# Shift_register.net
KiCad netlist of a schematic drawn in Altium Designer
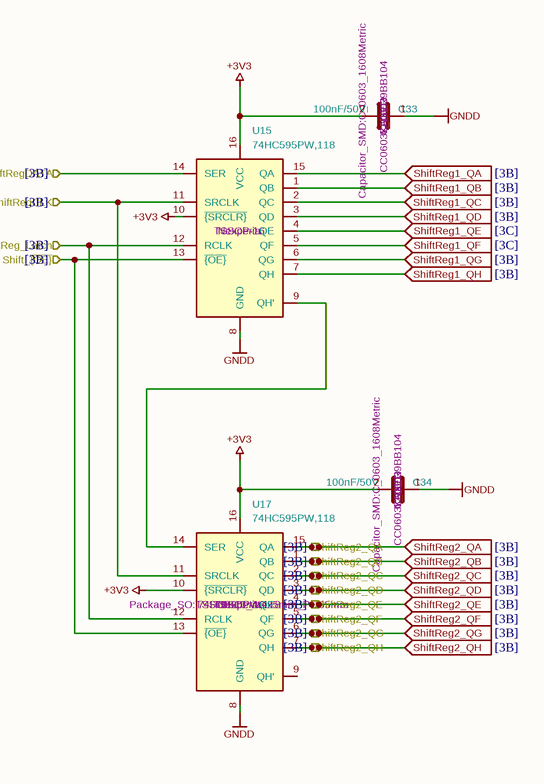
[diagram p0: Shift register.SchDoc]

(export (version "E")
  (design (tool "Eeschema 10.0.6"))
  (components
    (comp (ref "C33")
      (value "100nF/50V")
      (footprint "Capacitor_SMD:C_0603_1608Metric")
      (fields
        (field (name "MP") "CC0603KRX7R9BB104")
        (field (name "MF") "YAGEO")
        (field (name "PACKAGE") "C_0603")
      )
      (libsource (lib "Device") (part "C"))
    )
    (comp (ref "C34")
      (value "100nF/50V")
      (footprint "Capacitor_SMD:C_0603_1608Metric")
      (fields
        (field (name "MP") "CC0603KRX7R9BB104")
        (field (name "MF") "YAGEO")
        (field (name "PACKAGE") "C_0603")
      )
      (libsource (lib "Device") (part "C"))
    )
    (comp (ref "U15")
      (value "74HC595PW,118")
      (footprint "TSSOP-16_4.4x5mm_P0.65mm")
      (fields (field (name "MF") "Nexperia") (field (name "PACKAGE") "TSSOP-16"))
      (libsource (lib "74xx") (part "74HC595"))
    )
    (comp (ref "U17")
      (value "74HC595PW,118")
      (footprint "Package_SO:TSSOP-16_4.4x5mm_P0.65mm")
      (fields
        (field (name "MP") "74HC595PW,118")
        (field (name "MF") "Nexperia")
        (field (name "PACKAGE") "TSSOP-16")
      )
      (libsource (lib "74xx") (part "74HC595"))
    )
  )
  (nets
    (net (code "1") (name "+3V3") (class "Default")
      (node (ref "C33") (pin "2") (pinfunction "2_2") (pintype "passive"))
      (node (ref "C34") (pin "2") (pinfunction "2_2") (pintype "passive"))
      (node (ref "U15") (pin "10") (pinfunction "~{{SRCLR}}_10") (pintype "passive"))
      (node (ref "U15") (pin "16") (pinfunction "VCC_16") (pintype "passive"))
      (node (ref "U17") (pin "10") (pinfunction "~{{SRCLR}}_10") (pintype "passive"))
      (node (ref "U17") (pin "16") (pinfunction "VCC_16") (pintype "passive"))
    )
    (net (code "2") (name "/ShiftReg1_QA") (class "Default")
      (node (ref "U15") (pin "15") (pinfunction "QA_15") (pintype "passive"))
    )
    (net (code "3") (name "/ShiftReg1_QB") (class "Default")
      (node (ref "U15") (pin "1") (pinfunction "QB_1") (pintype "passive"))
    )
    (net (code "4") (name "/ShiftReg1_QC") (class "Default")
      (node (ref "U15") (pin "2") (pinfunction "QC_2") (pintype "passive"))
    )
    (net (code "5") (name "/ShiftReg1_QD") (class "Default")
      (node (ref "U15") (pin "3") (pinfunction "QD_3") (pintype "passive"))
    )
    (net (code "6") (name "/ShiftReg1_QE") (class "Default")
      (node (ref "U15") (pin "4") (pinfunction "QE_4") (pintype "passive"))
    )
    (net (code "7") (name "/ShiftReg1_QF") (class "Default")
      (node (ref "U15") (pin "5") (pinfunction "QF_5") (pintype "passive"))
    )
    (net (code "8") (name "/ShiftReg1_QG") (class "Default")
      (node (ref "U15") (pin "6") (pinfunction "QG_6") (pintype "passive"))
    )
    (net (code "9") (name "/ShiftReg1_QH") (class "Default")
      (node (ref "U15") (pin "7") (pinfunction "QH_7") (pintype "passive"))
    )
    (net (code "10") (name "/ShiftReg2_QA") (class "Default")
      (node (ref "U17") (pin "15") (pinfunction "QA_15") (pintype "passive"))
    )
    (net (code "11") (name "/ShiftReg2_QB") (class "Default")
      (node (ref "U17") (pin "1") (pinfunction "QB_1") (pintype "passive"))
    )
    (net (code "12") (name "/ShiftReg2_QC") (class "Default")
      (node (ref "U17") (pin "2") (pinfunction "QC_2") (pintype "passive"))
    )
    (net (code "13") (name "/ShiftReg2_QD") (class "Default")
      (node (ref "U17") (pin "3") (pinfunction "QD_3") (pintype "passive"))
    )
    (net (code "14") (name "/ShiftReg2_QE") (class "Default")
      (node (ref "U17") (pin "4") (pinfunction "QE_4") (pintype "passive"))
    )
    (net (code "15") (name "/ShiftReg2_QF") (class "Default")
      (node (ref "U17") (pin "5") (pinfunction "QF_5") (pintype "passive"))
    )
    (net (code "16") (name "/ShiftReg2_QG") (class "Default")
      (node (ref "U17") (pin "6") (pinfunction "QG_6") (pintype "passive"))
    )
    (net (code "17") (name "/ShiftReg2_QH") (class "Default")
      (node (ref "U17") (pin "7") (pinfunction "QH_7") (pintype "passive"))
    )
    (net (code "18") (name "/ShiftRegCLK") (class "Default")
      (node (ref "U15") (pin "11") (pinfunction "SRCLK_11") (pintype "passive"))
      (node (ref "U17") (pin "11") (pinfunction "SRCLK_11") (pintype "passive"))
    )
    (net (code "19") (name "/ShiftRegDATA") (class "Default")
      (node (ref "U15") (pin "14") (pinfunction "SER_14") (pintype "passive"))
    )
    (net (code "20") (name "/ShiftReg_Latch") (class "Default")
      (node (ref "U15") (pin "12") (pinfunction "RCLK_12") (pintype "passive"))
      (node (ref "U17") (pin "12") (pinfunction "RCLK_12") (pintype "passive"))
    )
    (net (code "21") (name "/Shift_~{{OE}}") (class "Default")
      (node (ref "U15") (pin "13") (pinfunction "~{{OE}}_13") (pintype "passive"))
      (node (ref "U17") (pin "13") (pinfunction "~{{OE}}_13") (pintype "passive"))
    )
    (net (code "22") (name "GNDD") (class "Default")
      (node (ref "C33") (pin "1") (pinfunction "1_1") (pintype "passive"))
      (node (ref "C34") (pin "1") (pinfunction "1_1") (pintype "passive"))
      (node (ref "U15") (pin "8") (pinfunction "GND_8") (pintype "passive"))
      (node (ref "U17") (pin "8") (pinfunction "GND_8") (pintype "passive"))
    )
    (net (code "23") (name "Net-(U15-QH')") (class "Default")
      (node (ref "U15") (pin "9") (pinfunction "QH'_9") (pintype "passive"))
      (node (ref "U17") (pin "14") (pinfunction "SER_14") (pintype "passive"))
    )
    (net (code "24") (name "unconnected-(U17-QH'-Pad9)") (class "Default")
      (node (ref "U17") (pin "9") (pinfunction "QH'_9") (pintype "passive"))
    )
  )
)
